# AD_info.net
KiCad netlist of a schematic drawn in Altium Designer
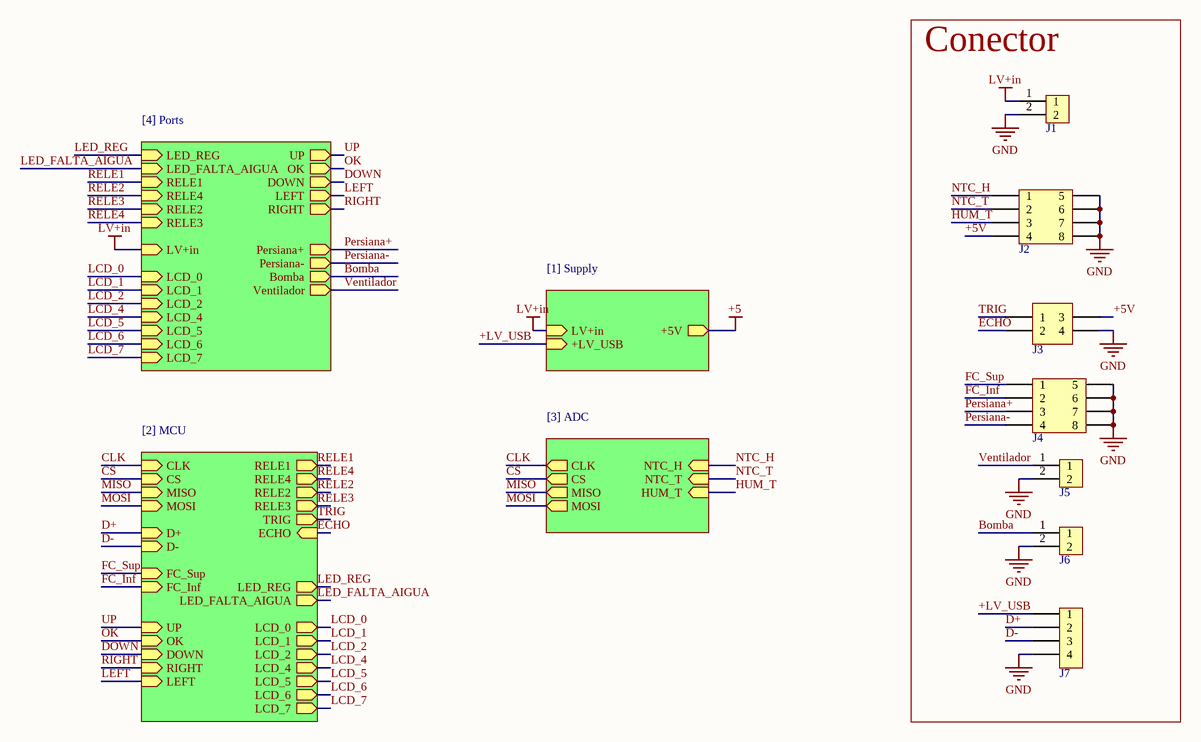
[diagram p0: AD_info.SchDoc]

(export (version "E")
  (design (tool "Eeschema 10.0.6"))
  (components
    (comp (ref "J1")
      (value "436500215")
      (footprint "J_MicroFit_2x1")
      (description "Header 1 Row Vertical Polarizing Peg 2 Pin SMT/Glow Wire Compatible Tin Plate")
      (libsource (lib "Electromechanical") (part "J_MicroFit_2x1"))
    )
    (comp (ref "J2")
      (value "105314-1108")
      (footprint "J_NanoFit_2X4")
      (description "Nano-Fit Right Angle Header Through Hole 2.50mm Pitch Dual Row 8 Circuits Tin (Sn) Plating Black")
      (fields (field (name "MANUFACTURER") "Molex") (field (name ".CREATOR") "DO"))
      (libsource (lib "Electromechanical") (part "J_NanoFit_2x4"))
    )
    (comp (ref "J3")
      (value "J_NanoFit_2x2")
      (footprint "J_NanoFit_2x2_v")
      (description "Conn Nano-Fit Power HDR 4 POS 2.5mm Solder ST Through Hole 4 Terminal Single Port Tray")
      (libsource (lib "Electromechanical") (part "J_NanoFit_2x2"))
    )
    (comp (ref "J4")
      (value "105314-1108")
      (footprint "J_NanoFit_2X4")
      (description "Nano-Fit Right Angle Header Through Hole 2.50mm Pitch Dual Row 8 Circuits Tin (Sn) Plating Black")
      (fields (field (name "MANUFACTURER") "Molex") (field (name ".CREATOR") "DO"))
      (libsource (lib "Electromechanical") (part "J_NanoFit_2x4"))
    )
    (comp (ref "J5")
      (value "436500215")
      (footprint "J_MicroFit_2x1")
      (description "Header 1 Row Vertical Polarizing Peg 2 Pin SMT/Glow Wire Compatible Tin Plate")
      (libsource (lib "Electromechanical") (part "J_MicroFit_2x1"))
    )
    (comp (ref "J6")
      (value "436500215")
      (footprint "J_MicroFit_2x1")
      (description "Header 1 Row Vertical Polarizing Peg 2 Pin SMT/Glow Wire Compatible Tin Plate")
      (libsource (lib "Electromechanical") (part "J_MicroFit_2x1"))
    )
    (comp (ref "J7")
      (value "61300411121")
      (footprint "J_PinHeader_1x4")
      (description "CONN HEADER 4 POS 2.54")
      (fields (field (name ".CREATOR") "AC"))
      (libsource (lib "Electromechanical") (part "J_UART"))
    )
  )
  (nets
    (net (code "2") (name "/+5V") (class "Default")
      (node (ref "J2") (pin "4") (pinfunction "4_4") (pintype "passive"))
      (node (ref "J3") (pin "3") (pinfunction "3_3") (pintype "passive"))
    )
    (net (code "3") (name "/+LV_USB") (class "Default")
      (node (ref "J7") (pin "1") (pinfunction "1_1") (pintype "passive"))
    )
    (net (code "4") (name "/Bomba") (class "Default")
      (node (ref "J6") (pin "1") (pinfunction "1_1") (pintype "passive"))
    )
    (net (code "7") (name "/D+") (class "Default")
      (node (ref "J7") (pin "2") (pinfunction "2_2") (pintype "passive"))
    )
    (net (code "8") (name "/D-") (class "Default")
      (node (ref "J7") (pin "3") (pinfunction "3_3") (pintype "passive"))
    )
    (net (code "10") (name "/ECHO") (class "Default")
      (node (ref "J3") (pin "2") (pinfunction "2_2") (pintype "passive"))
    )
    (net (code "11") (name "/FC_Inf") (class "Default")
      (node (ref "J4") (pin "2") (pinfunction "2_2") (pintype "passive"))
    )
    (net (code "12") (name "/FC_Sup") (class "Default")
      (node (ref "J4") (pin "1") (pinfunction "1_1") (pintype "passive"))
    )
    (net (code "13") (name "/HUM_T") (class "Default")
      (node (ref "J2") (pin "3") (pinfunction "3_3") (pintype "passive"))
    )
    (net (code "26") (name "/NTC_H") (class "Default")
      (node (ref "J2") (pin "1") (pinfunction "1_1") (pintype "passive"))
    )
    (net (code "27") (name "/NTC_T") (class "Default")
      (node (ref "J2") (pin "2") (pinfunction "2_2") (pintype "passive"))
    )
    (net (code "29") (name "/Persiana+") (class "Default")
      (node (ref "J4") (pin "3") (pinfunction "3_3") (pintype "passive"))
    )
    (net (code "30") (name "/Persiana-") (class "Default")
      (node (ref "J4") (pin "4") (pinfunction "4_4") (pintype "passive"))
    )
    (net (code "36") (name "/TRIG") (class "Default")
      (node (ref "J3") (pin "1") (pinfunction "1_1") (pintype "passive"))
    )
    (net (code "38") (name "/Ventilador") (class "Default")
      (node (ref "J5") (pin "1") (pinfunction "1_1") (pintype "passive"))
    )
    (net (code "39") (name "GND") (class "Default")
      (node (ref "J1") (pin "2") (pinfunction "2_2") (pintype "passive"))
      (node (ref "J2") (pin "5") (pinfunction "5_5") (pintype "passive"))
      (node (ref "J2") (pin "6") (pinfunction "6_6") (pintype "passive"))
      (node (ref "J2") (pin "7") (pinfunction "7_7") (pintype "passive"))
      (node (ref "J2") (pin "8") (pinfunction "8_8") (pintype "passive"))
      (node (ref "J3") (pin "4") (pinfunction "4_4") (pintype "passive"))
      (node (ref "J4") (pin "5") (pinfunction "5_5") (pintype "passive"))
      (node (ref "J4") (pin "6") (pinfunction "6_6") (pintype "passive"))
      (node (ref "J4") (pin "7") (pinfunction "7_7") (pintype "passive"))
      (node (ref "J4") (pin "8") (pinfunction "8_8") (pintype "passive"))
      (node (ref "J5") (pin "2") (pinfunction "2_2") (pintype "passive"))
      (node (ref "J6") (pin "2") (pinfunction "2_2") (pintype "passive"))
      (node (ref "J7") (pin "4") (pinfunction "4_4") (pintype "passive"))
    )
    (net (code "40") (name "LV+in") (class "Default")
      (node (ref "J1") (pin "1") (pinfunction "1_1") (pintype "passive"))
    )
  )
)
